# bbc_micro.net
KiCad netlist of a schematic drawn in EAGLE
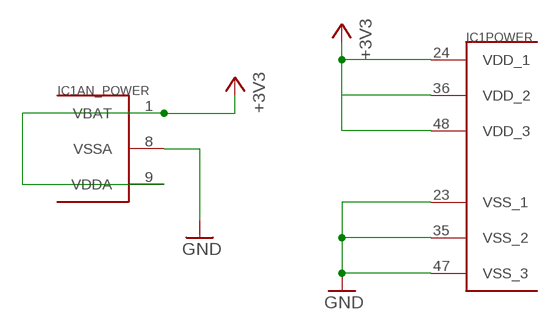
[diagram p0: schematic, sheet 1, part 1 of 2]
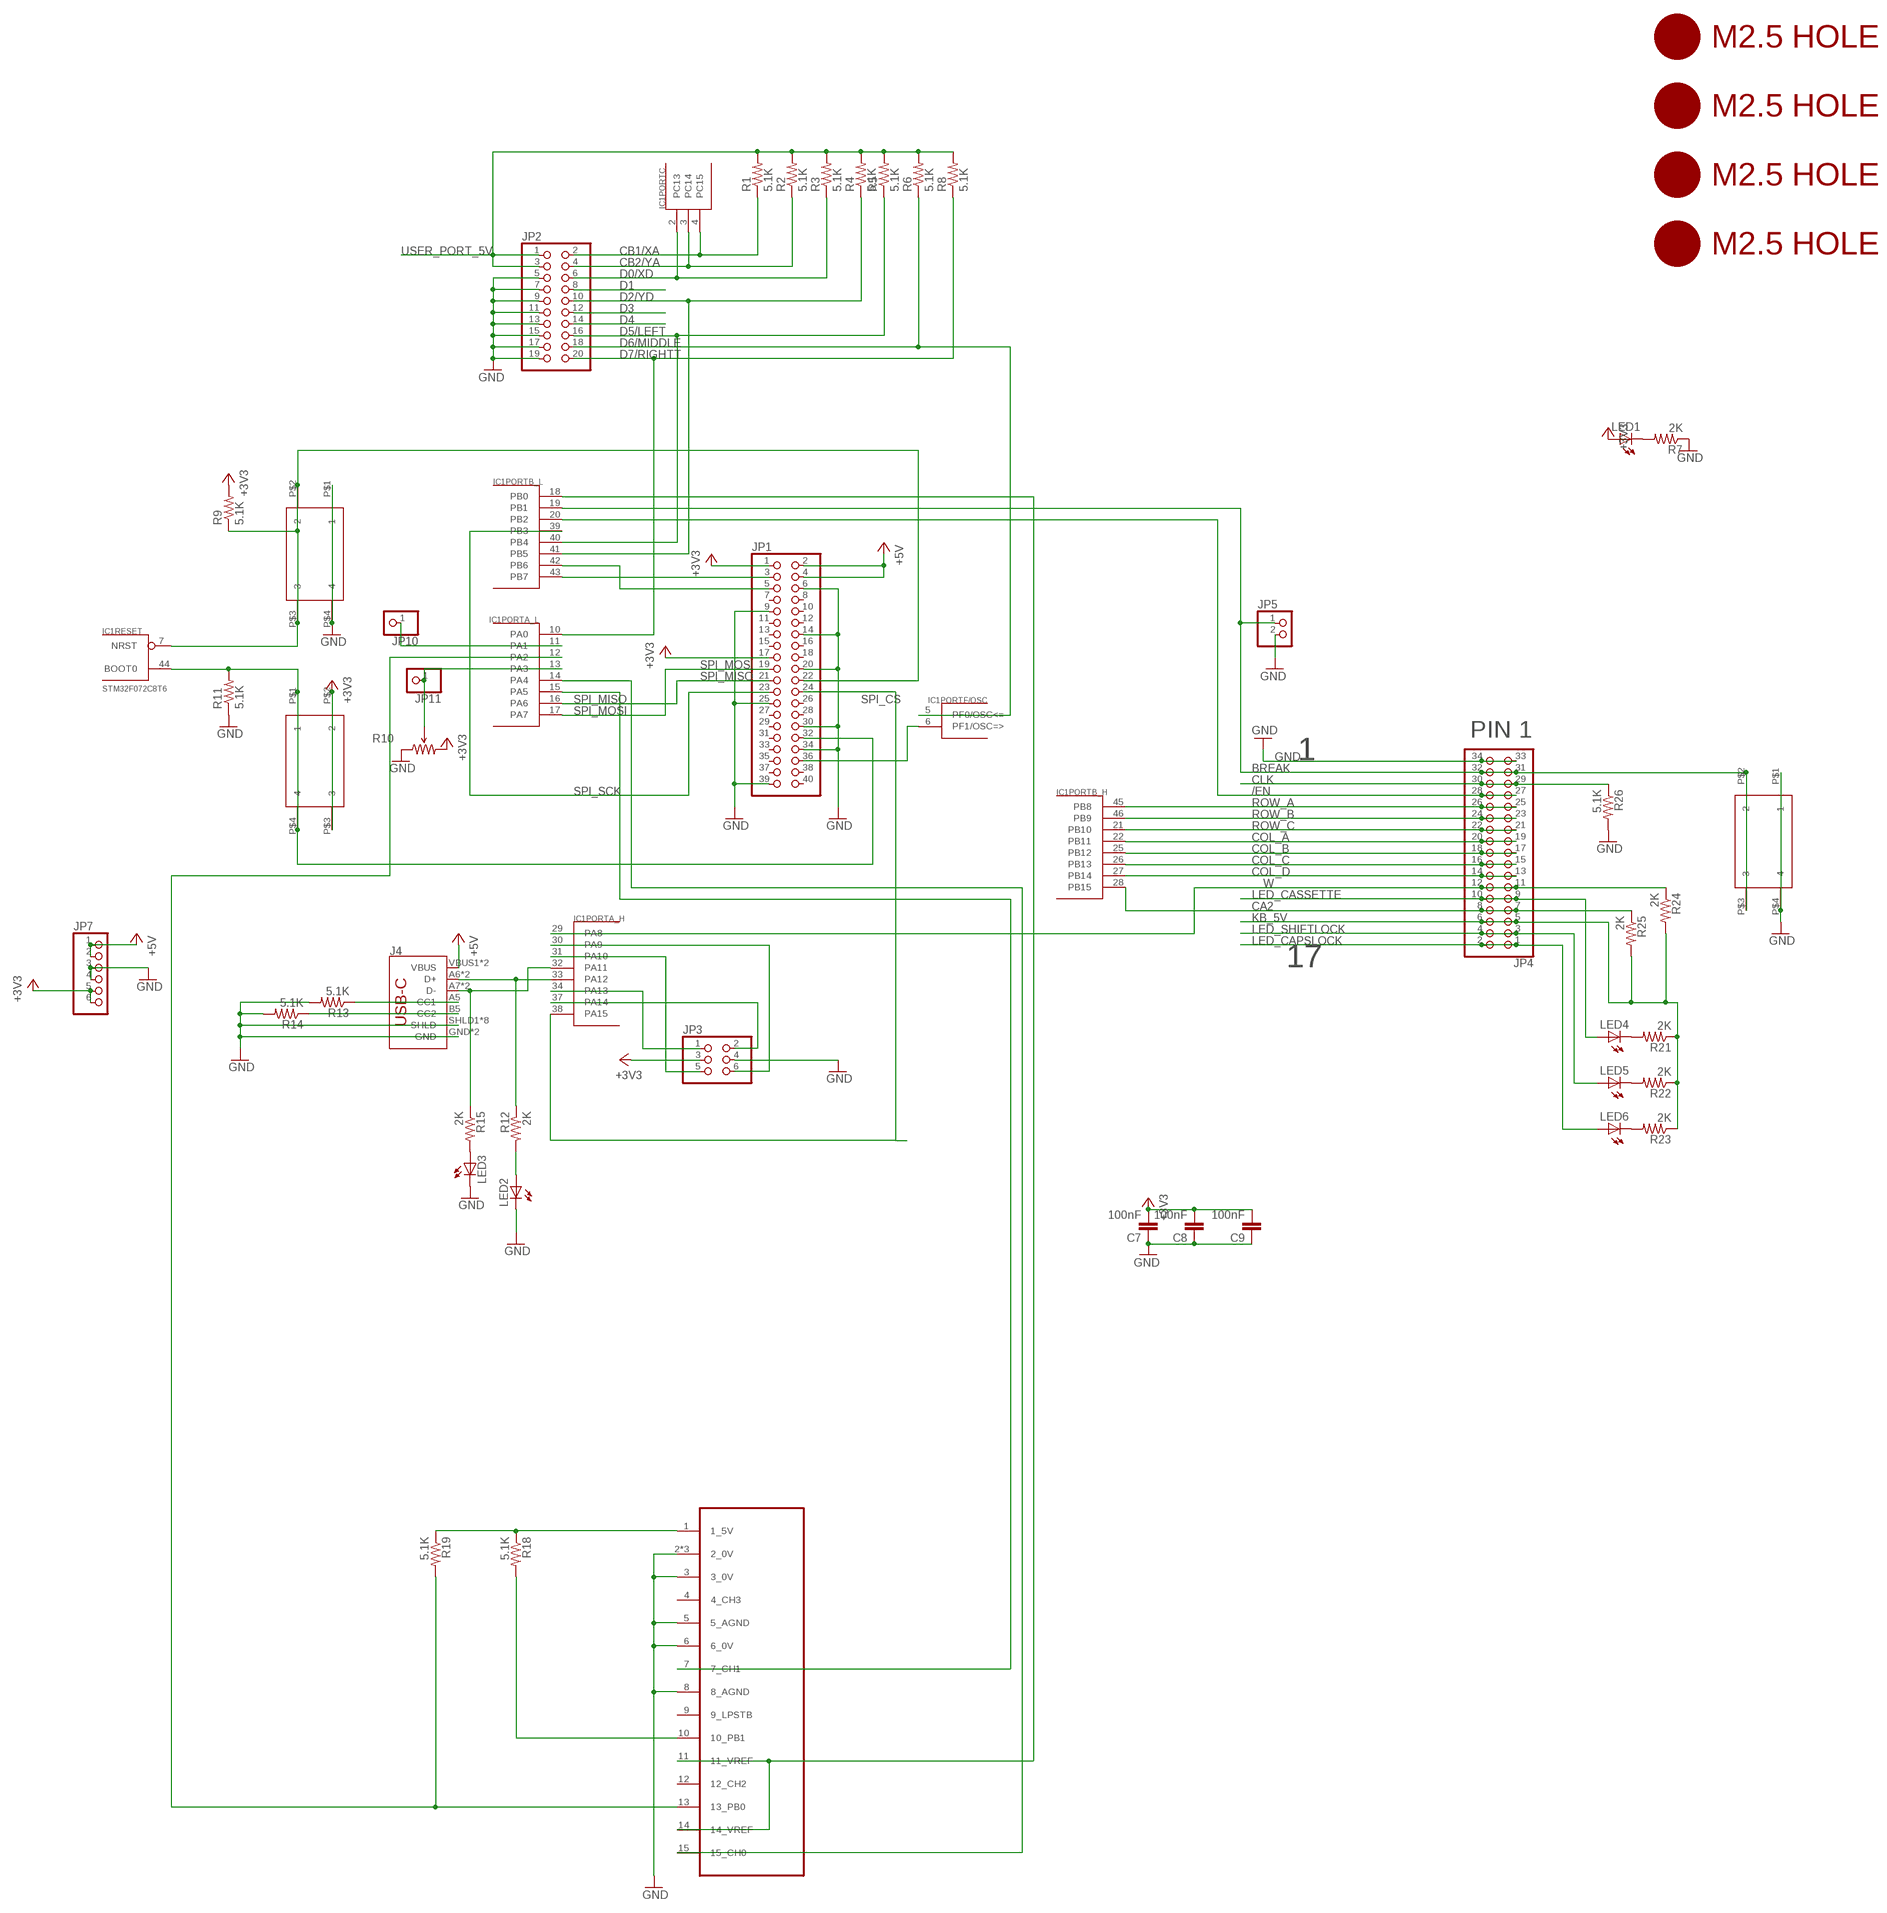
[diagram p1: schematic, sheet 1, part 2 of 2]

(export (version "E")
  (design (tool "Eeschema 10.0.6"))
  (components
    (comp (ref "C7")
      (value "100nF")
      (footprint "eagle-import:0805@1")
      (libsource (lib "eagle-import") (part "CAP0805"))
    )
    (comp (ref "C8")
      (value "100nF")
      (footprint "eagle-import:0805@1")
      (libsource (lib "eagle-import") (part "CAP0805"))
    )
    (comp (ref "C9")
      (value "100nF")
      (footprint "eagle-import:0805@1")
      (libsource (lib "eagle-import") (part "CAP0805"))
    )
    (comp (ref "IC1")
      (value "STM32F072C8T6")
      (footprint "eagle-import:TQFP48")
      (libsource (lib "eagle-import") (part "STM32F072C8T6"))
    )
    (comp (ref "J4")
      (value "USB_C16PIN")
      (footprint "eagle-import:USB-C-16P")
      (libsource (lib "eagle-import") (part "USB_C16PIN"))
    )
    (comp (ref "JP1")
      (value "PINHD-2X20-BIG")
      (footprint "eagle-import:2X20-BIG")
      (libsource (lib "eagle-import") (part "PINHD-2X20-BIG"))
    )
    (comp (ref "JP2")
      (value "PINHD-2X10/90")
      (footprint "eagle-import:2X10_90")
      (libsource (lib "eagle-import") (part "PINHD-2X10/90"))
    )
    (comp (ref "JP3")
      (value "PINHD-2X3")
      (footprint "eagle-import:2X03")
      (libsource (lib "eagle-import") (part "PINHD-2X3"))
    )
    (comp (ref "JP4")
      (value "PINHD-2X17/90")
      (footprint "eagle-import:2X17_90")
      (libsource (lib "eagle-import") (part "PINHD-2X17/90"))
    )
    (comp (ref "JP5")
      (value "PINHD-1X2")
      (footprint "eagle-import:1X02")
      (libsource (lib "eagle-import") (part "PINHD-1X2"))
    )
    (comp (ref "JP7")
      (value "PINHD-1X6CB")
      (footprint "eagle-import:1X06-CLEANBIG")
      (libsource (lib "eagle-import") (part "PINHD-1X6CB"))
    )
    (comp (ref "JP10")
      (value "PINHD-1X1CB")
      (footprint "eagle-import:1X01-CLEANBIG")
      (libsource (lib "eagle-import") (part "PINHD-1X1CB"))
    )
    (comp (ref "JP11")
      (value "PINHD-1X1CB")
      (footprint "eagle-import:1X01-CLEANBIG")
      (libsource (lib "eagle-import") (part "PINHD-1X1CB"))
    )
    (comp (ref "LED1")
      (value "LEDCHIP-LED0805")
      (footprint "eagle-import:CHIP-LED0805")
      (libsource (lib "eagle-import") (part "LEDCHIP-LED0805"))
    )
    (comp (ref "LED2")
      (value "LEDCHIP-LED0805")
      (footprint "eagle-import:CHIP-LED0805")
      (libsource (lib "eagle-import") (part "LEDCHIP-LED0805"))
    )
    (comp (ref "LED3")
      (value "LEDCHIP-LED0805")
      (footprint "eagle-import:CHIP-LED0805")
      (libsource (lib "eagle-import") (part "LEDCHIP-LED0805"))
    )
    (comp (ref "LED4")
      (value "LEDCHIP-LED0805")
      (footprint "eagle-import:CHIP-LED0805")
      (libsource (lib "eagle-import") (part "LEDCHIP-LED0805"))
    )
    (comp (ref "LED5")
      (value "LEDCHIP-LED0805")
      (footprint "eagle-import:CHIP-LED0805")
      (libsource (lib "eagle-import") (part "LEDCHIP-LED0805"))
    )
    (comp (ref "LED6")
      (value "LEDCHIP-LED0805")
      (footprint "eagle-import:CHIP-LED0805")
      (libsource (lib "eagle-import") (part "LEDCHIP-LED0805"))
    )
    (comp (ref "R1")
      (value "5.1K")
      (footprint "eagle-import:0805")
      (libsource (lib "eagle-import") (part "RESISTOR0805-RES"))
    )
    (comp (ref "R2")
      (value "5.1K")
      (footprint "eagle-import:0805")
      (libsource (lib "eagle-import") (part "RESISTOR0805-RES"))
    )
    (comp (ref "R3")
      (value "5.1K")
      (footprint "eagle-import:0805")
      (libsource (lib "eagle-import") (part "RESISTOR0805-RES"))
    )
    (comp (ref "R4")
      (value "5.1K")
      (footprint "eagle-import:0805")
      (libsource (lib "eagle-import") (part "RESISTOR0805-RES"))
    )
    (comp (ref "R5")
      (value "5.1K")
      (footprint "eagle-import:0805")
      (libsource (lib "eagle-import") (part "RESISTOR0805-RES"))
    )
    (comp (ref "R6")
      (value "5.1K")
      (footprint "eagle-import:0805")
      (libsource (lib "eagle-import") (part "RESISTOR0805-RES"))
    )
    (comp (ref "R7")
      (value "2K")
      (footprint "eagle-import:0805")
      (libsource (lib "eagle-import") (part "RESISTOR0805-RES"))
    )
    (comp (ref "R8")
      (value "5.1K")
      (footprint "eagle-import:0805")
      (libsource (lib "eagle-import") (part "RESISTOR0805-RES"))
    )
    (comp (ref "R9")
      (value "5.1K")
      (footprint "eagle-import:0805")
      (libsource (lib "eagle-import") (part "RESISTOR0805-RES"))
    )
    (comp (ref "R10")
      (value "TRIMPOTPTH")
      (footprint "eagle-import:TRIM_POT_PTH")
      (libsource (lib "eagle-import") (part "TRIMPOTPTH"))
    )
    (comp (ref "R11")
      (value "5.1K")
      (footprint "eagle-import:0805")
      (libsource (lib "eagle-import") (part "RESISTOR0805-RES"))
    )
    (comp (ref "R12")
      (value "2K")
      (footprint "eagle-import:0805")
      (libsource (lib "eagle-import") (part "RESISTOR0805-RES"))
    )
    (comp (ref "R13")
      (value "5.1K")
      (footprint "eagle-import:0805")
      (libsource (lib "eagle-import") (part "RESISTOR0805-RES"))
    )
    (comp (ref "R14")
      (value "5.1K")
      (footprint "eagle-import:0805")
      (libsource (lib "eagle-import") (part "RESISTOR0805-RES"))
    )
    (comp (ref "R15")
      (value "2K")
      (footprint "eagle-import:0805")
      (libsource (lib "eagle-import") (part "RESISTOR0805-RES"))
    )
    (comp (ref "R18")
      (value "5.1K")
      (footprint "eagle-import:0805")
      (libsource (lib "eagle-import") (part "RESISTOR0805-RES"))
    )
    (comp (ref "R19")
      (value "5.1K")
      (footprint "eagle-import:0805")
      (libsource (lib "eagle-import") (part "RESISTOR0805-RES"))
    )
    (comp (ref "R21")
      (value "2K")
      (footprint "eagle-import:0805")
      (libsource (lib "eagle-import") (part "RESISTOR0805-RES"))
    )
    (comp (ref "R22")
      (value "2K")
      (footprint "eagle-import:0805")
      (libsource (lib "eagle-import") (part "RESISTOR0805-RES"))
    )
    (comp (ref "R23")
      (value "2K")
      (footprint "eagle-import:0805")
      (libsource (lib "eagle-import") (part "RESISTOR0805-RES"))
    )
    (comp (ref "R24")
      (value "2K")
      (footprint "eagle-import:0805")
      (libsource (lib "eagle-import") (part "RESISTOR0805-RES"))
    )
    (comp (ref "R25")
      (value "2K")
      (footprint "eagle-import:0805")
      (libsource (lib "eagle-import") (part "RESISTOR0805-RES"))
    )
    (comp (ref "R26")
      (value "5.1K")
      (footprint "eagle-import:0805")
      (libsource (lib "eagle-import") (part "RESISTOR0805-RES"))
    )
    (comp (ref "SW1")
      (value "324_SW")
      (footprint "eagle-import:342_SWICH_FOOT")
      (libsource (lib "eagle-import") (part "324_SW"))
    )
    (comp (ref "SW2")
      (value "324_SW")
      (footprint "eagle-import:342_SWICH_FOOT")
      (libsource (lib "eagle-import") (part "324_SW"))
    )
    (comp (ref "SW3")
      (value "324_SW")
      (footprint "eagle-import:342_SWICH_FOOT")
      (libsource (lib "eagle-import") (part "324_SW"))
    )
    (comp (ref "U$2")
      (value "M2.5HOLE")
      (footprint "eagle-import:M2.5HOLE")
      (libsource (lib "eagle-import") (part "M2.5HOLE"))
    )
    (comp (ref "U$3")
      (value "M2.5HOLE")
      (footprint "eagle-import:M2.5HOLE")
      (libsource (lib "eagle-import") (part "M2.5HOLE"))
    )
    (comp (ref "U$6")
      (value "M2.5HOLE")
      (footprint "eagle-import:M2.5HOLE")
      (libsource (lib "eagle-import") (part "M2.5HOLE"))
    )
    (comp (ref "U$7")
      (value "M2.5HOLE")
      (footprint "eagle-import:M2.5HOLE")
      (libsource (lib "eagle-import") (part "M2.5HOLE"))
    )
    (comp (ref "U$9")
      (value "BBC_15P")
      (footprint "eagle-import:DA15")
      (libsource (lib "eagle-import") (part "BBC_15P"))
    )
  )
  (nets
    (net (code "1") (name "+3V3") (class "Default")
      (node (ref "C7") (pin "2") (pinfunction "2_2") (pintype "passive"))
      (node (ref "C8") (pin "2") (pinfunction "2_2") (pintype "passive"))
      (node (ref "C9") (pin "2") (pinfunction "2_2") (pintype "passive"))
      (node (ref "IC1") (pin "1") (pinfunction "VBAT_1") (pintype "power_in"))
      (node (ref "IC1") (pin "24") (pinfunction "VDD_1_24") (pintype "power_in"))
      (node (ref "IC1") (pin "36") (pinfunction "VDD_2_36") (pintype "power_in"))
      (node (ref "IC1") (pin "48") (pinfunction "VDD_3_48") (pintype "power_in"))
      (node (ref "IC1") (pin "9") (pinfunction "VDDA_9") (pintype "power_in"))
      (node (ref "JP1") (pin "1") (pinfunction "1_1") (pintype "passive"))
      (node (ref "JP1") (pin "17") (pinfunction "17_17") (pintype "passive"))
      (node (ref "JP3") (pin "3") (pinfunction "3_3") (pintype "passive"))
      (node (ref "JP7") (pin "5") (pinfunction "5_5") (pintype "passive"))
      (node (ref "JP7") (pin "6") (pinfunction "6_6") (pintype "passive"))
      (node (ref "LED1") (pin "A") (pinfunction "A_A") (pintype "passive"))
      (node (ref "R10") (pin "3") (pinfunction "CW_3") (pintype "passive"))
      (node (ref "R9") (pin "2") (pinfunction "2_2") (pintype "passive"))
      (node (ref "SW2") (pin "P$2") (pinfunction "2_P$2") (pintype "bidirectional"))
      (node (ref "SW2") (pin "P$3") (pinfunction "3_P$3") (pintype "bidirectional"))
    )
    (net (code "2") (name "+5V") (class "Default")
      (node (ref "J4") (pin "VBUS1") (pinfunction "VBUS_VBUS1") (pintype "bidirectional"))
      (node (ref "J4") (pin "VBUS2") (pinfunction "VBUS_VBUS2") (pintype "bidirectional"))
      (node (ref "JP1") (pin "2") (pinfunction "2_2") (pintype "passive"))
      (node (ref "JP1") (pin "4") (pinfunction "4_4") (pintype "passive"))
      (node (ref "JP7") (pin "1") (pinfunction "1_1") (pintype "passive"))
      (node (ref "JP7") (pin "2") (pinfunction "2_2") (pintype "passive"))
    )
    (net (code "3") (name "/BREAK") (class "Default")
      (node (ref "IC1") (pin "19") (pinfunction "PB1_19") (pintype "bidirectional"))
      (node (ref "JP4") (pin "31") (pinfunction "31_31") (pintype "passive"))
      (node (ref "JP4") (pin "32") (pinfunction "32_32") (pintype "passive"))
      (node (ref "JP5") (pin "1") (pinfunction "1_1") (pintype "passive"))
      (node (ref "SW3") (pin "P$2") (pinfunction "2_P$2") (pintype "bidirectional"))
      (node (ref "SW3") (pin "P$3") (pinfunction "3_P$3") (pintype "bidirectional"))
    )
    (net (code "4") (name "/CA2") (class "Default")
      (node (ref "IC1") (pin "28") (pinfunction "PB15_28") (pintype "bidirectional"))
      (node (ref "JP4") (pin "7") (pinfunction "7_7") (pintype "passive"))
      (node (ref "JP4") (pin "8") (pinfunction "8_8") (pintype "passive"))
      (node (ref "R25") (pin "1") (pinfunction "1_1") (pintype "passive"))
    )
    (net (code "5") (name "/CB1{slash}XA") (class "Default")
      (node (ref "IC1") (pin "4") (pinfunction "PC15_4") (pintype "bidirectional"))
      (node (ref "JP2") (pin "2") (pinfunction "2_2") (pintype "passive"))
      (node (ref "R1") (pin "1") (pinfunction "1_1") (pintype "passive"))
    )
    (net (code "6") (name "/CB2{slash}YA") (class "Default")
      (node (ref "IC1") (pin "3") (pinfunction "PC14_3") (pintype "bidirectional"))
      (node (ref "JP2") (pin "4") (pinfunction "4_4") (pintype "passive"))
      (node (ref "R2") (pin "1") (pinfunction "1_1") (pintype "passive"))
    )
    (net (code "7") (name "/CLK") (class "Default")
      (node (ref "JP4") (pin "29") (pinfunction "29_29") (pintype "passive"))
      (node (ref "JP4") (pin "30") (pinfunction "30_30") (pintype "passive"))
      (node (ref "R26") (pin "1") (pinfunction "1_1") (pintype "passive"))
    )
    (net (code "8") (name "/COL_A") (class "Default")
      (node (ref "IC1") (pin "22") (pinfunction "PB11_22") (pintype "bidirectional"))
      (node (ref "JP4") (pin "19") (pinfunction "19_19") (pintype "passive"))
      (node (ref "JP4") (pin "20") (pinfunction "20_20") (pintype "passive"))
    )
    (net (code "9") (name "/COL_B") (class "Default")
      (node (ref "IC1") (pin "25") (pinfunction "PB12_25") (pintype "bidirectional"))
      (node (ref "JP4") (pin "17") (pinfunction "17_17") (pintype "passive"))
      (node (ref "JP4") (pin "18") (pinfunction "18_18") (pintype "passive"))
    )
    (net (code "10") (name "/COL_C") (class "Default")
      (node (ref "IC1") (pin "26") (pinfunction "PB13_26") (pintype "bidirectional"))
      (node (ref "JP4") (pin "15") (pinfunction "15_15") (pintype "passive"))
      (node (ref "JP4") (pin "16") (pinfunction "16_16") (pintype "passive"))
    )
    (net (code "11") (name "/COL_D") (class "Default")
      (node (ref "IC1") (pin "27") (pinfunction "PB14_27") (pintype "bidirectional"))
      (node (ref "JP4") (pin "13") (pinfunction "13_13") (pintype "passive"))
      (node (ref "JP4") (pin "14") (pinfunction "14_14") (pintype "passive"))
    )
    (net (code "12") (name "/D0{slash}XD") (class "Default")
      (node (ref "IC1") (pin "2") (pinfunction "PC13_2") (pintype "bidirectional"))
      (node (ref "JP2") (pin "6") (pinfunction "6_6") (pintype "passive"))
      (node (ref "R3") (pin "1") (pinfunction "1_1") (pintype "passive"))
    )
    (net (code "13") (name "/D1") (class "Default")
      (node (ref "JP2") (pin "8") (pinfunction "8_8") (pintype "passive"))
    )
    (net (code "14") (name "/D2{slash}YD") (class "Default")
      (node (ref "IC1") (pin "41") (pinfunction "PB5_41") (pintype "bidirectional"))
      (node (ref "JP2") (pin "10") (pinfunction "10_10") (pintype "passive"))
      (node (ref "R4") (pin "1") (pinfunction "1_1") (pintype "passive"))
    )
    (net (code "15") (name "/D3") (class "Default")
      (node (ref "JP2") (pin "12") (pinfunction "12_12") (pintype "passive"))
    )
    (net (code "16") (name "/D4") (class "Default")
      (node (ref "JP2") (pin "14") (pinfunction "14_14") (pintype "passive"))
    )
    (net (code "17") (name "/D5{slash}LEFT") (class "Default")
      (node (ref "IC1") (pin "40") (pinfunction "PB4_40") (pintype "bidirectional"))
      (node (ref "JP2") (pin "16") (pinfunction "16_16") (pintype "passive"))
      (node (ref "R5") (pin "1") (pinfunction "1_1") (pintype "passive"))
    )
    (net (code "18") (name "/D6{slash}MIDDLE") (class "Default")
      (node (ref "IC1") (pin "5") (pinfunction "PF0/OSC<=_5") (pintype "bidirectional"))
      (node (ref "JP2") (pin "18") (pinfunction "18_18") (pintype "passive"))
      (node (ref "R6") (pin "1") (pinfunction "1_1") (pintype "passive"))
    )
    (net (code "19") (name "/D7{slash}RIGHTT") (class "Default")
      (node (ref "IC1") (pin "10") (pinfunction "PA0_10") (pintype "bidirectional"))
      (node (ref "JP2") (pin "20") (pinfunction "20_20") (pintype "passive"))
      (node (ref "R8") (pin "1") (pinfunction "1_1") (pintype "passive"))
    )
    (net (code "20") (name "/KB_5V") (class "Default")
      (node (ref "JP4") (pin "5") (pinfunction "5_5") (pintype "passive"))
      (node (ref "JP4") (pin "6") (pinfunction "6_6") (pintype "passive"))
      (node (ref "R21") (pin "1") (pinfunction "1_1") (pintype "passive"))
      (node (ref "R22") (pin "1") (pinfunction "1_1") (pintype "passive"))
      (node (ref "R23") (pin "1") (pinfunction "1_1") (pintype "passive"))
      (node (ref "R24") (pin "2") (pinfunction "2_2") (pintype "passive"))
      (node (ref "R25") (pin "2") (pinfunction "2_2") (pintype "passive"))
    )
    (net (code "21") (name "/LED_CAPSLOCK") (class "Default")
      (node (ref "JP4") (pin "1") (pinfunction "1_1") (pintype "passive"))
      (node (ref "JP4") (pin "2") (pinfunction "2_2") (pintype "passive"))
      (node (ref "LED6") (pin "A") (pinfunction "A_A") (pintype "passive"))
    )
    (net (code "22") (name "/LED_CASSETTE") (class "Default")
      (node (ref "JP4") (pin "10") (pinfunction "10_10") (pintype "passive"))
      (node (ref "JP4") (pin "9") (pinfunction "9_9") (pintype "passive"))
      (node (ref "LED4") (pin "A") (pinfunction "A_A") (pintype "passive"))
    )
    (net (code "23") (name "/LED_SHIFTLOCK") (class "Default")
      (node (ref "JP4") (pin "3") (pinfunction "3_3") (pintype "passive"))
      (node (ref "JP4") (pin "4") (pinfunction "4_4") (pintype "passive"))
      (node (ref "LED5") (pin "A") (pinfunction "A_A") (pintype "passive"))
    )
    (net (code "24") (name "/ROW_A") (class "Default")
      (node (ref "IC1") (pin "45") (pinfunction "PB8_45") (pintype "bidirectional"))
      (node (ref "JP4") (pin "25") (pinfunction "25_25") (pintype "passive"))
      (node (ref "JP4") (pin "26") (pinfunction "26_26") (pintype "passive"))
    )
    (net (code "25") (name "/ROW_B") (class "Default")
      (node (ref "IC1") (pin "46") (pinfunction "PB9_46") (pintype "bidirectional"))
      (node (ref "JP4") (pin "23") (pinfunction "23_23") (pintype "passive"))
      (node (ref "JP4") (pin "24") (pinfunction "24_24") (pintype "passive"))
    )
    (net (code "26") (name "/ROW_C") (class "Default")
      (node (ref "IC1") (pin "21") (pinfunction "PB10_21") (pintype "bidirectional"))
      (node (ref "JP4") (pin "21") (pinfunction "21_21") (pintype "passive"))
      (node (ref "JP4") (pin "22") (pinfunction "22_22") (pintype "passive"))
    )
    (net (code "27") (name "/SPI_CS") (class "Default")
      (node (ref "IC1") (pin "38") (pinfunction "PA15_38") (pintype "bidirectional"))
      (node (ref "JP1") (pin "24") (pinfunction "24_24") (pintype "passive"))
    )
    (net (code "28") (name "/SPI_MISO") (class "Default")
      (node (ref "IC1") (pin "16") (pinfunction "PA6_16") (pintype "bidirectional"))
      (node (ref "JP1") (pin "21") (pinfunction "21_21") (pintype "passive"))
    )
    (net (code "29") (name "/SPI_MOSI") (class "Default")
      (node (ref "IC1") (pin "17") (pinfunction "PA7_17") (pintype "bidirectional"))
      (node (ref "JP1") (pin "19") (pinfunction "19_19") (pintype "passive"))
    )
    (net (code "30") (name "/SPI_SCK") (class "Default")
      (node (ref "IC1") (pin "39") (pinfunction "PB3_39") (pintype "bidirectional"))
      (node (ref "JP1") (pin "23") (pinfunction "23_23") (pintype "passive"))
    )
    (net (code "31") (name "/USER_PORT_5V") (class "Default")
      (node (ref "JP2") (pin "1") (pinfunction "1_1") (pintype "passive"))
      (node (ref "JP2") (pin "3") (pinfunction "3_3") (pintype "passive"))
      (node (ref "R1") (pin "2") (pinfunction "2_2") (pintype "passive"))
      (node (ref "R2") (pin "2") (pinfunction "2_2") (pintype "passive"))
      (node (ref "R3") (pin "2") (pinfunction "2_2") (pintype "passive"))
      (node (ref "R4") (pin "2") (pinfunction "2_2") (pintype "passive"))
      (node (ref "R5") (pin "2") (pinfunction "2_2") (pintype "passive"))
      (node (ref "R6") (pin "2") (pinfunction "2_2") (pintype "passive"))
      (node (ref "R8") (pin "2") (pinfunction "2_2") (pintype "passive"))
    )
    (net (code "32") (name "/W") (class "Default")
      (node (ref "IC1") (pin "29") (pinfunction "PA8_29") (pintype "bidirectional"))
      (node (ref "JP4") (pin "11") (pinfunction "11_11") (pintype "passive"))
      (node (ref "JP4") (pin "12") (pinfunction "12_12") (pintype "passive"))
      (node (ref "R24") (pin "1") (pinfunction "1_1") (pintype "passive"))
    )
    (net (code "33") (name "/{slash}EN") (class "Default")
      (node (ref "IC1") (pin "20") (pinfunction "PB2_20") (pintype "bidirectional"))
      (node (ref "JP4") (pin "27") (pinfunction "27_27") (pintype "passive"))
      (node (ref "JP4") (pin "28") (pinfunction "28_28") (pintype "passive"))
    )
    (net (code "34") (name "GND") (class "Default")
      (node (ref "C7") (pin "1") (pinfunction "1_1") (pintype "passive"))
      (node (ref "C8") (pin "1") (pinfunction "1_1") (pintype "passive"))
      (node (ref "C9") (pin "1") (pinfunction "1_1") (pintype "passive"))
      (node (ref "IC1") (pin "23") (pinfunction "VSS_1_23") (pintype "power_in"))
      (node (ref "IC1") (pin "35") (pinfunction "VSS_2_35") (pintype "power_in"))
      (node (ref "IC1") (pin "47") (pinfunction "VSS_3_47") (pintype "power_in"))
      (node (ref "IC1") (pin "8") (pinfunction "VSSA_8") (pintype "power_in"))
      (node (ref "J4") (pin "GND") (pinfunction "GND_GND") (pintype "bidirectional"))
      (node (ref "J4") (pin "GND2") (pinfunction "GND_GND2") (pintype "bidirectional"))
      (node (ref "J4") (pin "SHLD1") (pinfunction "SHLD_SHLD1") (pintype "bidirectional"))
      (node (ref "J4") (pin "SHLD2") (pinfunction "SHLD_SHLD2") (pintype "bidirectional"))
      (node (ref "J4") (pin "SHLD3") (pinfunction "SHLD_SHLD3") (pintype "bidirectional"))
      (node (ref "J4") (pin "SHLD4") (pinfunction "SHLD_SHLD4") (pintype "bidirectional"))
      (node (ref "J4") (pin "SHLD5") (pinfunction "SHLD_SHLD5") (pintype "bidirectional"))
      (node (ref "J4") (pin "SHLD6") (pinfunction "SHLD_SHLD6") (pintype "bidirectional"))
      (node (ref "J4") (pin "SHLD7") (pinfunction "SHLD_SHLD7") (pintype "bidirectional"))
      (node (ref "J4") (pin "SHLD8") (pinfunction "SHLD_SHLD8") (pintype "bidirectional"))
      (node (ref "JP1") (pin "14") (pinfunction "14_14") (pintype "passive"))
      (node (ref "JP1") (pin "20") (pinfunction "20_20") (pintype "passive"))
      (node (ref "JP1") (pin "25") (pinfunction "25_25") (pintype "passive"))
      (node (ref "JP1") (pin "30") (pinfunction "30_30") (pintype "passive"))
      (node (ref "JP1") (pin "34") (pinfunction "34_34") (pintype "passive"))
      (node (ref "JP1") (pin "39") (pinfunction "39_39") (pintype "passive"))
      (node (ref "JP1") (pin "6") (pinfunction "6_6") (pintype "passive"))
      (node (ref "JP1") (pin "9") (pinfunction "9_9") (pintype "passive"))
      (node (ref "JP2") (pin "11") (pinfunction "11_11") (pintype "passive"))
      (node (ref "JP2") (pin "13") (pinfunction "13_13") (pintype "passive"))
      (node (ref "JP2") (pin "15") (pinfunction "15_15") (pintype "passive"))
      (node (ref "JP2") (pin "17") (pinfunction "17_17") (pintype "passive"))
      (node (ref "JP2") (pin "19") (pinfunction "19_19") (pintype "passive"))
      (node (ref "JP2") (pin "5") (pinfunction "5_5") (pintype "passive"))
      (node (ref "JP2") (pin "7") (pinfunction "7_7") (pintype "passive"))
      (node (ref "JP2") (pin "9") (pinfunction "9_9") (pintype "passive"))
      (node (ref "JP3") (pin "4") (pinfunction "4_4") (pintype "passive"))
      (node (ref "JP4") (pin "33") (pinfunction "33_33") (pintype "passive"))
      (node (ref "JP4") (pin "34") (pinfunction "34_34") (pintype "passive"))
      (node (ref "JP5") (pin "2") (pinfunction "2_2") (pintype "passive"))
      (node (ref "JP7") (pin "3") (pinfunction "3_3") (pintype "passive"))
      (node (ref "JP7") (pin "4") (pinfunction "4_4") (pintype "passive"))
      (node (ref "LED2") (pin "C") (pinfunction "C_C") (pintype "passive"))
      (node (ref "LED3") (pin "C") (pinfunction "C_C") (pintype "passive"))
      (node (ref "R10") (pin "1") (pinfunction "CCW_1") (pintype "passive"))
      (node (ref "R11") (pin "1") (pinfunction "1_1") (pintype "passive"))
      (node (ref "R13") (pin "2") (pinfunction "2_2") (pintype "passive"))
      (node (ref "R14") (pin "2") (pinfunction "2_2") (pintype "passive"))
      (node (ref "R26") (pin "2") (pinfunction "2_2") (pintype "passive"))
      (node (ref "R7") (pin "1") (pinfunction "1_1") (pintype "passive"))
      (node (ref "SW1") (pin "P$1") (pinfunction "1_P$1") (pintype "bidirectional"))
      (node (ref "SW1") (pin "P$4") (pinfunction "4_P$4") (pintype "bidirectional"))
      (node (ref "SW3") (pin "P$1") (pinfunction "1_P$1") (pintype "bidirectional"))
      (node (ref "SW3") (pin "P$4") (pinfunction "4_P$4") (pintype "bidirectional"))
      (node (ref "U$9") (pin "2") (pinfunction "2_0V_2") (pintype "bidirectional"))
      (node (ref "U$9") (pin "3") (pinfunction "3_0V_3") (pintype "bidirectional"))
      (node (ref "U$9") (pin "5") (pinfunction "5_AGND_5") (pintype "bidirectional"))
      (node (ref "U$9") (pin "6") (pinfunction "6_0V_6") (pintype "bidirectional"))
      (node (ref "U$9") (pin "8") (pinfunction "8_AGND_8") (pintype "bidirectional"))
      (node (ref "U$9") (pin "G1") (pinfunction "2_0V_G1") (pintype "bidirectional"))
      (node (ref "U$9") (pin "G2") (pinfunction "2_0V_G2") (pintype "bidirectional"))
    )
    (net (code "35") (name "Net-(IC1B-PA9)") (class "Default")
      (node (ref "IC1") (pin "30") (pinfunction "PA9_30") (pintype "bidirectional"))
      (node (ref "JP3") (pin "6") (pinfunction "6_6") (pintype "passive"))
    )
    (net (code "36") (name "Net-(IC1B-PA10)") (class "Default")
      (node (ref "IC1") (pin "31") (pinfunction "PA10_31") (pintype "bidirectional"))
      (node (ref "JP3") (pin "5") (pinfunction "5_5") (pintype "passive"))
    )
    (net (code "37") (name "Net-(IC1B-PA11)") (class "Default")
      (node (ref "IC1") (pin "32") (pinfunction "PA11_32") (pintype "bidirectional"))
      (node (ref "J4") (pin "A7") (pinfunction "D-_A7") (pintype "bidirectional"))
      (node (ref "J4") (pin "B7") (pinfunction "D-_B7") (pintype "bidirectional"))
      (node (ref "R15") (pin "1") (pinfunction "1_1") (pintype "passive"))
    )
    (net (code "38") (name "Net-(IC1B-PA12)") (class "Default")
      (node (ref "IC1") (pin "33") (pinfunction "PA12_33") (pintype "bidirectional"))
      (node (ref "J4") (pin "A6") (pinfunction "D+_A6") (pintype "bidirectional"))
      (node (ref "J4") (pin "B6") (pinfunction "D+_B6") (pintype "bidirectional"))
      (node (ref "R12") (pin "1") (pinfunction "1_1") (pintype "passive"))
    )
    (net (code "39") (name "Net-(IC1B-PA13)") (class "Default")
      (node (ref "IC1") (pin "34") (pinfunction "PA13_34") (pintype "bidirectional"))
      (node (ref "JP3") (pin "1") (pinfunction "1_1") (pintype "passive"))
    )
    (net (code "40") (name "Net-(IC1B-PA14)") (class "Default")
      (node (ref "IC1") (pin "37") (pinfunction "PA14_37") (pintype "bidirectional"))
      (node (ref "JP3") (pin "2") (pinfunction "2_2") (pintype "passive"))
    )
    (net (code "41") (name "Net-(IC1C-PA1)") (class "Default")
      (node (ref "IC1") (pin "11") (pinfunction "PA1_11") (pintype "bidirectional"))
      (node (ref "JP10") (pin "1") (pinfunction "1_1") (pintype "passive"))
    )
    (net (code "42") (name "Net-(IC1C-PA2)") (class "Default")
      (node (ref "IC1") (pin "12") (pinfunction "PA2_12") (pintype "bidirectional"))
      (node (ref "R19") (pin "2") (pinfunction "2_2") (pintype "passive"))
      (node (ref "U$9") (pin "13") (pinfunction "13_PB0_13") (pintype "bidirectional"))
    )
    (net (code "43") (name "Net-(IC1C-PA3)") (class "Default")
      (node (ref "IC1") (pin "13") (pinfunction "PA3_13") (pintype "bidirectional"))
      (node (ref "JP11") (pin "1") (pinfunction "1_1") (pintype "passive"))
      (node (ref "R10") (pin "2") (pinfunction "WIPER_2") (pintype "passive"))
    )
    (net (code "44") (name "Net-(IC1C-PA4)") (class "Default")
      (node (ref "IC1") (pin "14") (pinfunction "PA4_14") (pintype "bidirectional"))
      (node (ref "U$9") (pin "15") (pinfunction "15_CH0_15") (pintype "bidirectional"))
    )
    (net (code "45") (name "Net-(IC1C-PA5)") (class "Default")
      (node (ref "IC1") (pin "15") (pinfunction "PA5_15") (pintype "bidirectional"))
      (node (ref "U$9") (pin "7") (pinfunction "7_CH1_7") (pintype "bidirectional"))
    )
    (net (code "46") (name "Net-(IC1E-PB0)") (class "Default")
      (node (ref "IC1") (pin "18") (pinfunction "PB0_18") (pintype "bidirectional"))
      (node (ref "U$9") (pin "11") (pinfunction "11_VREF_11") (pintype "bidirectional"))
      (node (ref "U$9") (pin "14") (pinfunction "14_VREF_14") (pintype "bidirectional"))
    )
    (net (code "47") (name "Net-(IC1E-PB6)") (class "Default")
      (node (ref "IC1") (pin "42") (pinfunction "PB6_42") (pintype "bidirectional"))
      (node (ref "JP1") (pin "5") (pinfunction "5_5") (pintype "passive"))
    )
    (net (code "48") (name "Net-(IC1E-PB7)") (class "Default")
      (node (ref "IC1") (pin "43") (pinfunction "PB7_43") (pintype "bidirectional"))
      (node (ref "JP1") (pin "3") (pinfunction "3_3") (pintype "passive"))
    )
    (net (code "49") (name "Net-(IC1G-PF1{slash}OSC=>)") (class "Default")
      (node (ref "IC1") (pin "6") (pinfunction "PF1/OSC=>_6") (pintype "bidirectional"))
      (node (ref "JP1") (pin "36") (pinfunction "36_36") (pintype "passive"))
    )
    (net (code "50") (name "Net-(IC1I-BOOT0)") (class "Default")
      (node (ref "IC1") (pin "44") (pinfunction "BOOT0_44") (pintype "input"))
      (node (ref "JP1") (pin "32") (pinfunction "32_32") (pintype "passive"))
      (node (ref "R11") (pin "2") (pinfunction "2_2") (pintype "passive"))
      (node (ref "SW2") (pin "P$1") (pinfunction "1_P$1") (pintype "bidirectional"))
      (node (ref "SW2") (pin "P$4") (pinfunction "4_P$4") (pintype "bidirectional"))
    )
    (net (code "51") (name "Net-(IC1I-NRST)") (class "Default")
      (node (ref "IC1") (pin "7") (pinfunction "NRST_7") (pintype "input"))
      (node (ref "JP1") (pin "22") (pinfunction "22_22") (pintype "passive"))
      (node (ref "R9") (pin "1") (pinfunction "1_1") (pintype "passive"))
      (node (ref "SW1") (pin "P$2") (pinfunction "2_P$2") (pintype "bidirectional"))
      (node (ref "SW1") (pin "P$3") (pinfunction "3_P$3") (pintype "bidirectional"))
    )
    (net (code "52") (name "Net-(J4-CC1)") (class "Default")
      (node (ref "J4") (pin "A5") (pinfunction "CC1_A5") (pintype "bidirectional"))
      (node (ref "R13") (pin "1") (pinfunction "1_1") (pintype "passive"))
    )
    (net (code "53") (name "Net-(J4-CC2)") (class "Default")
      (node (ref "J4") (pin "B5") (pinfunction "CC2_B5") (pintype "bidirectional"))
      (node (ref "R14") (pin "1") (pinfunction "1_1") (pintype "passive"))
    )
    (net (code "54") (name "Net-(LED1-PadC)") (class "Default")
      (node (ref "LED1") (pin "C") (pinfunction "C_C") (pintype "passive"))
      (node (ref "R7") (pin "2") (pinfunction "2_2") (pintype "passive"))
    )
    (net (code "55") (name "Net-(LED2-PadA)") (class "Default")
      (node (ref "LED2") (pin "A") (pinfunction "A_A") (pintype "passive"))
      (node (ref "R12") (pin "2") (pinfunction "2_2") (pintype "passive"))
    )
    (net (code "56") (name "Net-(LED3-PadA)") (class "Default")
      (node (ref "LED3") (pin "A") (pinfunction "A_A") (pintype "passive"))
      (node (ref "R15") (pin "2") (pinfunction "2_2") (pintype "passive"))
    )
    (net (code "57") (name "Net-(LED4-PadC)") (class "Default")
      (node (ref "LED4") (pin "C") (pinfunction "C_C") (pintype "passive"))
      (node (ref "R21") (pin "2") (pinfunction "2_2") (pintype "passive"))
    )
    (net (code "58") (name "Net-(LED5-PadC)") (class "Default")
      (node (ref "LED5") (pin "C") (pinfunction "C_C") (pintype "passive"))
      (node (ref "R22") (pin "2") (pinfunction "2_2") (pintype "passive"))
    )
    (net (code "59") (name "Net-(LED6-PadC)") (class "Default")
      (node (ref "LED6") (pin "C") (pinfunction "C_C") (pintype "passive"))
      (node (ref "R23") (pin "2") (pinfunction "2_2") (pintype "passive"))
    )
    (net (code "60") (name "Net-(U$9-1_5V)") (class "Default")
      (node (ref "R18") (pin "1") (pinfunction "1_1") (pintype "passive"))
      (node (ref "R19") (pin "1") (pinfunction "1_1") (pintype "passive"))
      (node (ref "U$9") (pin "1") (pinfunction "1_5V_1") (pintype "bidirectional"))
    )
    (net (code "61") (name "Net-(U$9-10_PB1)") (class "Default")
      (node (ref "R18") (pin "2") (pinfunction "2_2") (pintype "passive"))
      (node (ref "U$9") (pin "10") (pinfunction "10_PB1_10") (pintype "bidirectional"))
    )
    (net (code "62") (name "unconnected-(JP1-Pad7)") (class "Default")
      (node (ref "JP1") (pin "7") (pinfunction "7_7") (pintype "passive"))
    )
    (net (code "63") (name "unconnected-(JP1-Pad8)") (class "Default")
      (node (ref "JP1") (pin "8") (pinfunction "8_8") (pintype "passive"))
    )
    (net (code "64") (name "unconnected-(JP1-Pad10)") (class "Default")
      (node (ref "JP1") (pin "10") (pinfunction "10_10") (pintype "passive"))
    )
    (net (code "65") (name "unconnected-(JP1-Pad11)") (class "Default")
      (node (ref "JP1") (pin "11") (pinfunction "11_11") (pintype "passive"))
    )
    (net (code "66") (name "unconnected-(JP1-Pad12)") (class "Default")
      (node (ref "JP1") (pin "12") (pinfunction "12_12") (pintype "passive"))
    )
    (net (code "67") (name "unconnected-(JP1-Pad13)") (class "Default")
      (node (ref "JP1") (pin "13") (pinfunction "13_13") (pintype "passive"))
    )
    (net (code "68") (name "unconnected-(JP1-Pad15)") (class "Default")
      (node (ref "JP1") (pin "15") (pinfunction "15_15") (pintype "passive"))
    )
    (net (code "69") (name "unconnected-(JP1-Pad16)") (class "Default")
      (node (ref "JP1") (pin "16") (pinfunction "16_16") (pintype "passive"))
    )
    (net (code "70") (name "unconnected-(JP1-Pad18)") (class "Default")
      (node (ref "JP1") (pin "18") (pinfunction "18_18") (pintype "passive"))
    )
    (net (code "71") (name "unconnected-(JP1-Pad26)") (class "Default")
      (node (ref "JP1") (pin "26") (pinfunction "26_26") (pintype "passive"))
    )
    (net (code "72") (name "unconnected-(JP1-Pad27)") (class "Default")
      (node (ref "JP1") (pin "27") (pinfunction "27_27") (pintype "passive"))
    )
    (net (code "73") (name "unconnected-(JP1-Pad28)") (class "Default")
      (node (ref "JP1") (pin "28") (pinfunction "28_28") (pintype "passive"))
    )
    (net (code "74") (name "unconnected-(JP1-Pad29)") (class "Default")
      (node (ref "JP1") (pin "29") (pinfunction "29_29") (pintype "passive"))
    )
    (net (code "75") (name "unconnected-(JP1-Pad31)") (class "Default")
      (node (ref "JP1") (pin "31") (pinfunction "31_31") (pintype "passive"))
    )
    (net (code "76") (name "unconnected-(JP1-Pad33)") (class "Default")
      (node (ref "JP1") (pin "33") (pinfunction "33_33") (pintype "passive"))
    )
    (net (code "77") (name "unconnected-(JP1-Pad35)") (class "Default")
      (node (ref "JP1") (pin "35") (pinfunction "35_35") (pintype "passive"))
    )
    (net (code "78") (name "unconnected-(JP1-Pad37)") (class "Default")
      (node (ref "JP1") (pin "37") (pinfunction "37_37") (pintype "passive"))
    )
    (net (code "79") (name "unconnected-(JP1-Pad38)") (class "Default")
      (node (ref "JP1") (pin "38") (pinfunction "38_38") (pintype "passive"))
    )
    (net (code "80") (name "unconnected-(JP1-Pad40)") (class "Default")
      (node (ref "JP1") (pin "40") (pinfunction "40_40") (pintype "passive"))
    )
    (net (code "81") (name "unconnected-(U$9-4_CH3-Pad4)") (class "Default")
      (node (ref "U$9") (pin "4") (pinfunction "4_CH3_4") (pintype "bidirectional"))
    )
    (net (code "82") (name "unconnected-(U$9-9_LPSTB-Pad9)") (class "Default")
      (node (ref "U$9") (pin "9") (pinfunction "9_LPSTB_9") (pintype "bidirectional"))
    )
    (net (code "83") (name "unconnected-(U$9-12_CH2-Pad12)") (class "Default")
      (node (ref "U$9") (pin "12") (pinfunction "12_CH2_12") (pintype "bidirectional"))
    )
  )
)
